# AAS_touch_board_rev1_0.net
KiCad netlist of a schematic drawn in Altium Designer
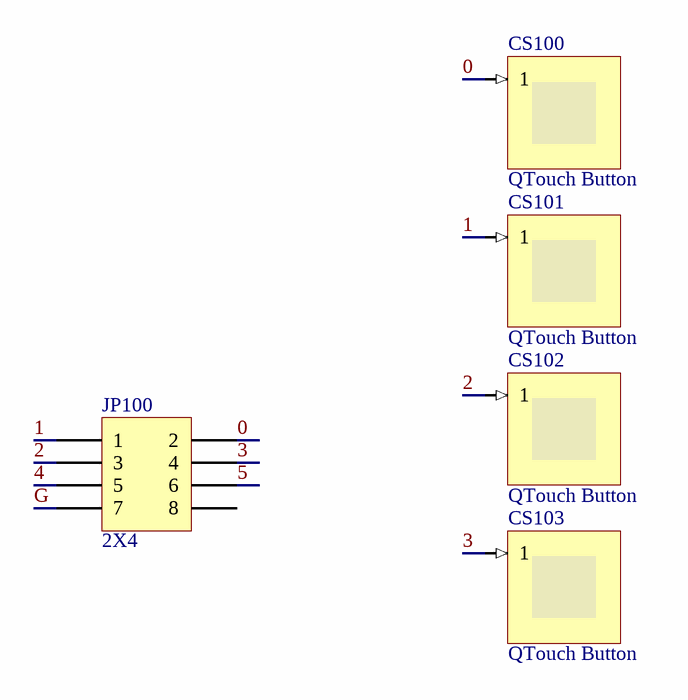
[diagram p0: AAS_touch_board_rev1_0.SchDoc]

(export (version "E")
  (design (tool "Eeschema 10.0.6"))
  (components
    (comp (ref "CS100") (value "QTouch Button") (libsource (lib "Atmel QTouch") (part "QTouchButton")))
    (comp (ref "CS101") (value "QTouch Button") (libsource (lib "Atmel QTouch") (part "QTouchButton")))
    (comp (ref "CS102") (value "QTouch Button") (libsource (lib "Atmel QTouch") (part "QTouchButton")))
    (comp (ref "CS103") (value "QTouch Button") (libsource (lib "Atmel QTouch") (part "QTouchButton")))
    (comp (ref "JP100")
      (value "2X4")
      (footprint "HDR2X4_P2")
      (description "Header, 8-Pin, Dual row")
      (libsource (lib "SmartSys") (part "Header 2X4"))
    )
  )
  (nets
    (net (code "1") (name "/0") (class "Default")
      (node (ref "CS100") (pin "1") (pinfunction "1_1") (pintype "input"))
      (node (ref "JP100") (pin "2") (pinfunction "2_2") (pintype "passive"))
    )
    (net (code "2") (name "/1") (class "Default")
      (node (ref "CS101") (pin "1") (pinfunction "1_1") (pintype "input"))
      (node (ref "JP100") (pin "1") (pinfunction "1_1") (pintype "passive"))
    )
    (net (code "3") (name "/2") (class "Default")
      (node (ref "CS102") (pin "1") (pinfunction "1_1") (pintype "input"))
      (node (ref "JP100") (pin "3") (pinfunction "3_3") (pintype "passive"))
    )
    (net (code "4") (name "/3") (class "Default")
      (node (ref "CS103") (pin "1") (pinfunction "1_1") (pintype "input"))
      (node (ref "JP100") (pin "4") (pinfunction "4_4") (pintype "passive"))
    )
    (net (code "5") (name "/4") (class "Default")
      (node (ref "JP100") (pin "5") (pinfunction "5_5") (pintype "passive"))
    )
    (net (code "6") (name "/5") (class "Default")
      (node (ref "JP100") (pin "6") (pinfunction "6_6") (pintype "passive"))
    )
    (net (code "7") (name "/G") (class "Default")
      (node (ref "JP100") (pin "7") (pinfunction "7_7") (pintype "passive"))
    )
    (net (code "8") (name "unconnected-(JP100-Pad8)") (class "Default")
      (node (ref "JP100") (pin "8") (pinfunction "8_8") (pintype "passive"))
    )
  )
)
